# capMet.net
KiCad netlist of a schematic drawn in EAGLE
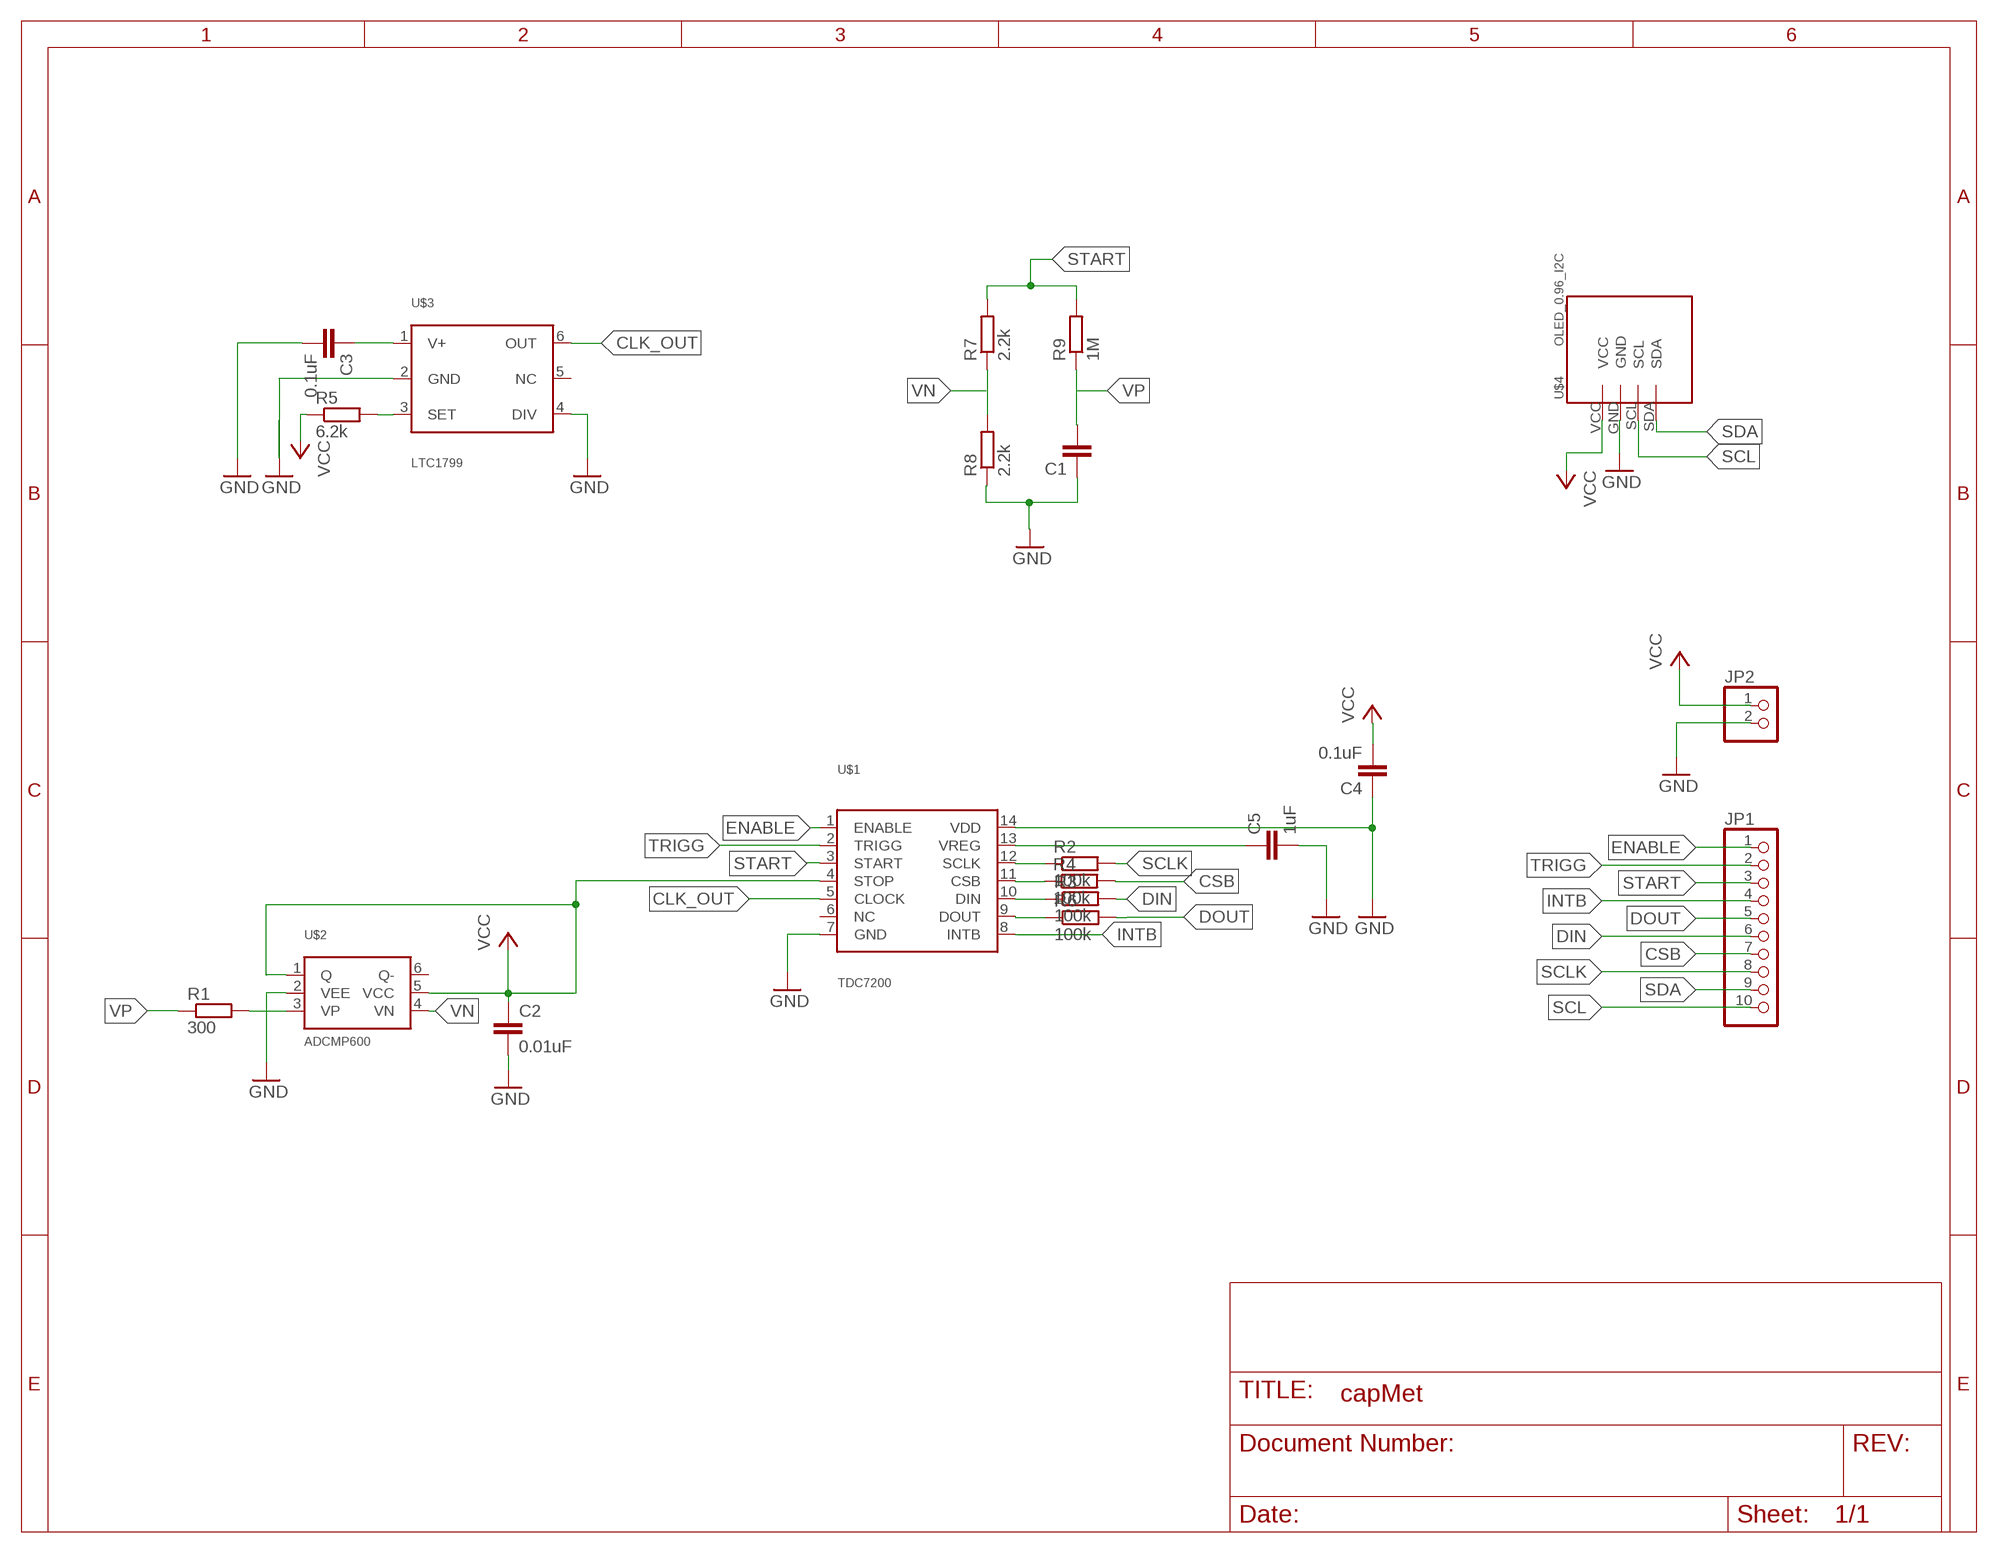
[diagram p0: schematic, sheet 1]

(export (version "E")
  (design (tool "Eeschema 10.0.6"))
  (components
    (comp (ref "C1")
      (value "C-EUC0805")
      (footprint "eagle-import:C0805")
      (libsource (lib "eagle-import") (part "C-EUC0805"))
    )
    (comp (ref "C2")
      (value "0.01uF")
      (footprint "eagle-import:C0805")
      (libsource (lib "eagle-import") (part "C-EUC0805"))
    )
    (comp (ref "C3")
      (value "0.1uF")
      (footprint "eagle-import:C0805")
      (libsource (lib "eagle-import") (part "C-EUC0805"))
    )
    (comp (ref "C4")
      (value "0.1uF")
      (footprint "eagle-import:C0805")
      (libsource (lib "eagle-import") (part "C-EUC0805"))
    )
    (comp (ref "C5")
      (value "1uF")
      (footprint "eagle-import:C0805")
      (libsource (lib "eagle-import") (part "C-EUC0805"))
    )
    (comp (ref "JP1")
      (value "PINHD-1X10")
      (footprint "eagle-import:1X10")
      (libsource (lib "eagle-import") (part "PINHD-1X10"))
    )
    (comp (ref "JP2")
      (value "PINHD-1X2")
      (footprint "eagle-import:1X02")
      (libsource (lib "eagle-import") (part "PINHD-1X2"))
    )
    (comp (ref "R1")
      (value "300")
      (footprint "eagle-import:R0805")
      (libsource (lib "eagle-import") (part "R-EU_R0805"))
    )
    (comp (ref "R2")
      (value "100k")
      (footprint "eagle-import:R0805")
      (libsource (lib "eagle-import") (part "R-EU_R0805"))
    )
    (comp (ref "R3")
      (value "100k")
      (footprint "eagle-import:R0805")
      (libsource (lib "eagle-import") (part "R-EU_R0805"))
    )
    (comp (ref "R4")
      (value "100k")
      (footprint "eagle-import:R0805")
      (libsource (lib "eagle-import") (part "R-EU_R0805"))
    )
    (comp (ref "R5")
      (value "6.2k")
      (footprint "eagle-import:R0805")
      (libsource (lib "eagle-import") (part "R-EU_R0805"))
    )
    (comp (ref "R6")
      (value "100k")
      (footprint "eagle-import:R0805")
      (libsource (lib "eagle-import") (part "R-EU_R0805"))
    )
    (comp (ref "R7")
      (value "2.2k")
      (footprint "eagle-import:R0805")
      (libsource (lib "eagle-import") (part "R-EU_R0805"))
    )
    (comp (ref "R8")
      (value "2.2k")
      (footprint "eagle-import:R0805")
      (libsource (lib "eagle-import") (part "R-EU_R0805"))
    )
    (comp (ref "R9")
      (value "1M")
      (footprint "eagle-import:R0805")
      (libsource (lib "eagle-import") (part "R-EU_R0805"))
    )
    (comp (ref "U$1")
      (value "TDC7200")
      (footprint "eagle-import:TSSOP14")
      (libsource (lib "eagle-import") (part "TDC7200"))
    )
    (comp (ref "U$2")
      (value "ADCMP600")
      (footprint "eagle-import:SC70-6")
      (libsource (lib "eagle-import") (part "ADCMP600"))
    )
    (comp (ref "U$3")
      (value "LTC1799")
      (footprint "eagle-import:TSOT23-6")
      (libsource (lib "eagle-import") (part "LTC1799"))
    )
    (comp (ref "U$4")
      (value "OLED_0.96_I2C")
      (footprint "eagle-import:OLED_0.96_I2C")
      (libsource (lib "eagle-import") (part "OLED_0.96_I2C"))
    )
  )
  (nets
    (net (code "1") (name "CLK_OUT") (class "Default")
      (node (ref "U$3") (pin "6") (pinfunction "OUT_6") (pintype "bidirectional"))
    )
    (net (code "2") (name "CSB") (class "Default")
      (node (ref "JP1") (pin "7") (pinfunction "7_7") (pintype "passive"))
      (node (ref "R4") (pin "2") (pinfunction "2_2") (pintype "passive"))
    )
    (net (code "3") (name "DIN") (class "Default")
      (node (ref "JP1") (pin "6") (pinfunction "6_6") (pintype "passive"))
      (node (ref "R3") (pin "2") (pinfunction "2_2") (pintype "passive"))
    )
    (net (code "4") (name "DOUT") (class "Default")
      (node (ref "JP1") (pin "5") (pinfunction "5_5") (pintype "passive"))
      (node (ref "R6") (pin "2") (pinfunction "2_2") (pintype "passive"))
    )
    (net (code "5") (name "ENABLE") (class "Default")
      (node (ref "JP1") (pin "1") (pinfunction "1_1") (pintype "passive"))
      (node (ref "U$1") (pin "1") (pinfunction "ENABLE_1") (pintype "bidirectional"))
    )
    (net (code "6") (name "GND") (class "Default")
      (node (ref "C1") (pin "1") (pinfunction "1_1") (pintype "passive"))
      (node (ref "C2") (pin "2") (pinfunction "2_2") (pintype "passive"))
      (node (ref "C3") (pin "2") (pinfunction "2_2") (pintype "passive"))
      (node (ref "C5") (pin "2") (pinfunction "2_2") (pintype "passive"))
      (node (ref "JP2") (pin "2") (pinfunction "2_2") (pintype "passive"))
      (node (ref "R8") (pin "1") (pinfunction "1_1") (pintype "passive"))
      (node (ref "U$1") (pin "7") (pinfunction "GND_7") (pintype "bidirectional"))
      (node (ref "U$2") (pin "2") (pinfunction "VEE_2") (pintype "bidirectional"))
      (node (ref "U$3") (pin "2") (pinfunction "GND_2") (pintype "bidirectional"))
      (node (ref "U$3") (pin "4") (pinfunction "DIV_4") (pintype "bidirectional"))
      (node (ref "U$4") (pin "GND") (pinfunction "GND_GND") (pintype "bidirectional"))
    )
    (net (code "7") (name "INTB") (class "Default")
      (node (ref "JP1") (pin "4") (pinfunction "4_4") (pintype "passive"))
      (node (ref "U$1") (pin "8") (pinfunction "INTB_8") (pintype "bidirectional"))
    )
    (net (code "8") (name "Net-(C1-Pad2)") (class "Default")
      (node (ref "C1") (pin "2") (pinfunction "2_2") (pintype "passive"))
      (node (ref "R9") (pin "1") (pinfunction "1_1") (pintype "passive"))
    )
    (net (code "9") (name "Net-(R7-Pad1)") (class "Default")
      (node (ref "R7") (pin "1") (pinfunction "1_1") (pintype "passive"))
      (node (ref "R8") (pin "2") (pinfunction "2_2") (pintype "passive"))
    )
    (net (code "10") (name "Net-(U$1-DOUT)") (class "Default")
      (node (ref "R6") (pin "1") (pinfunction "1_1") (pintype "passive"))
      (node (ref "U$1") (pin "9") (pinfunction "DOUT_9") (pintype "bidirectional"))
    )
    (net (code "11") (name "Net-(U$1-STOP)") (class "Default")
      (node (ref "U$1") (pin "4") (pinfunction "STOP_4") (pintype "bidirectional"))
      (node (ref "U$2") (pin "1") (pinfunction "Q_1") (pintype "bidirectional"))
    )
    (net (code "12") (name "Net-(U$1-VDD)") (class "Default")
      (node (ref "C4") (pin "1") (pinfunction "1_1") (pintype "passive"))
      (node (ref "U$1") (pin "14") (pinfunction "VDD_14") (pintype "bidirectional"))
    )
    (net (code "13") (name "Net-(U$1-VREG)") (class "Default")
      (node (ref "C5") (pin "1") (pinfunction "1_1") (pintype "passive"))
      (node (ref "U$1") (pin "13") (pinfunction "VREG_13") (pintype "bidirectional"))
    )
    (net (code "14") (name "Net-(U$2-VP)") (class "Default")
      (node (ref "R1") (pin "2") (pinfunction "2_2") (pintype "passive"))
      (node (ref "U$2") (pin "3") (pinfunction "VP_3") (pintype "bidirectional"))
    )
    (net (code "15") (name "Net-(U$3-SET)") (class "Default")
      (node (ref "R5") (pin "2") (pinfunction "2_2") (pintype "passive"))
      (node (ref "U$3") (pin "3") (pinfunction "SET_3") (pintype "bidirectional"))
    )
    (net (code "16") (name "Net-(U$3-V+)") (class "Default")
      (node (ref "C3") (pin "1") (pinfunction "1_1") (pintype "passive"))
      (node (ref "U$3") (pin "1") (pinfunction "V+_1") (pintype "bidirectional"))
    )
    (net (code "17") (name "SCL") (class "Default")
      (node (ref "JP1") (pin "10") (pinfunction "10_10") (pintype "passive"))
      (node (ref "U$4") (pin "SCL") (pinfunction "SCL_SCL") (pintype "bidirectional"))
    )
    (net (code "18") (name "SCLK") (class "Default")
      (node (ref "JP1") (pin "8") (pinfunction "8_8") (pintype "passive"))
      (node (ref "R2") (pin "2") (pinfunction "2_2") (pintype "passive"))
    )
    (net (code "19") (name "SDA") (class "Default")
      (node (ref "JP1") (pin "9") (pinfunction "9_9") (pintype "passive"))
      (node (ref "U$4") (pin "SDA") (pinfunction "SDA_SDA") (pintype "bidirectional"))
    )
    (net (code "20") (name "START") (class "Default")
      (node (ref "JP1") (pin "3") (pinfunction "3_3") (pintype "passive"))
      (node (ref "R7") (pin "2") (pinfunction "2_2") (pintype "passive"))
      (node (ref "R9") (pin "2") (pinfunction "2_2") (pintype "passive"))
      (node (ref "U$1") (pin "3") (pinfunction "START_3") (pintype "bidirectional"))
    )
    (net (code "21") (name "TRIGG") (class "Default")
      (node (ref "JP1") (pin "2") (pinfunction "2_2") (pintype "passive"))
      (node (ref "U$1") (pin "2") (pinfunction "TRIGG_2") (pintype "bidirectional"))
    )
    (net (code "22") (name "VCC") (class "Default")
      (node (ref "C2") (pin "1") (pinfunction "1_1") (pintype "passive"))
      (node (ref "C4") (pin "2") (pinfunction "2_2") (pintype "passive"))
      (node (ref "JP2") (pin "1") (pinfunction "1_1") (pintype "passive"))
      (node (ref "R5") (pin "1") (pinfunction "1_1") (pintype "passive"))
      (node (ref "U$2") (pin "5") (pinfunction "VCC_5") (pintype "bidirectional"))
      (node (ref "U$4") (pin "VCC") (pinfunction "VCC_VCC") (pintype "bidirectional"))
    )
    (net (code "23") (name "VN") (class "Default")
      (node (ref "U$2") (pin "4") (pinfunction "VN_4") (pintype "bidirectional"))
    )
    (net (code "24") (name "VP") (class "Default")
      (node (ref "R1") (pin "1") (pinfunction "1_1") (pintype "passive"))
    )
    (net (code "25") (name "unconnected-(R2-Pad1)") (class "Default")
      (node (ref "R2") (pin "1") (pinfunction "1_1") (pintype "passive"))
    )
    (net (code "26") (name "unconnected-(R3-Pad1)") (class "Default")
      (node (ref "R3") (pin "1") (pinfunction "1_1") (pintype "passive"))
    )
    (net (code "27") (name "unconnected-(R4-Pad1)") (class "Default")
      (node (ref "R4") (pin "1") (pinfunction "1_1") (pintype "passive"))
    )
    (net (code "28") (name "unconnected-(U$1-CLOCK-Pad5)") (class "Default")
      (node (ref "U$1") (pin "5") (pinfunction "CLOCK_5") (pintype "bidirectional"))
    )
    (net (code "29") (name "unconnected-(U$1-CSB-Pad11)") (class "Default")
      (node (ref "U$1") (pin "11") (pinfunction "CSB_11") (pintype "bidirectional"))
    )
    (net (code "30") (name "unconnected-(U$1-DIN-Pad10)") (class "Default")
      (node (ref "U$1") (pin "10") (pinfunction "DIN_10") (pintype "bidirectional"))
    )
    (net (code "31") (name "unconnected-(U$1-NC-Pad6)") (class "Default")
      (node (ref "U$1") (pin "6") (pinfunction "NC_6") (pintype "bidirectional"))
    )
    (net (code "32") (name "unconnected-(U$1-SCLK-Pad12)") (class "Default")
      (node (ref "U$1") (pin "12") (pinfunction "SCLK_12") (pintype "bidirectional"))
    )
    (net (code "33") (name "unconnected-(U$2-Q--Pad6)") (class "Default")
      (node (ref "U$2") (pin "6") (pinfunction "Q-_6") (pintype "bidirectional"))
    )
    (net (code "34") (name "unconnected-(U$3-NC-Pad5)") (class "Default")
      (node (ref "U$3") (pin "5") (pinfunction "NC_5") (pintype "bidirectional"))
    )
  )
)
